# main_scheme.net
KiCad netlist of a schematic drawn in Altium Designer
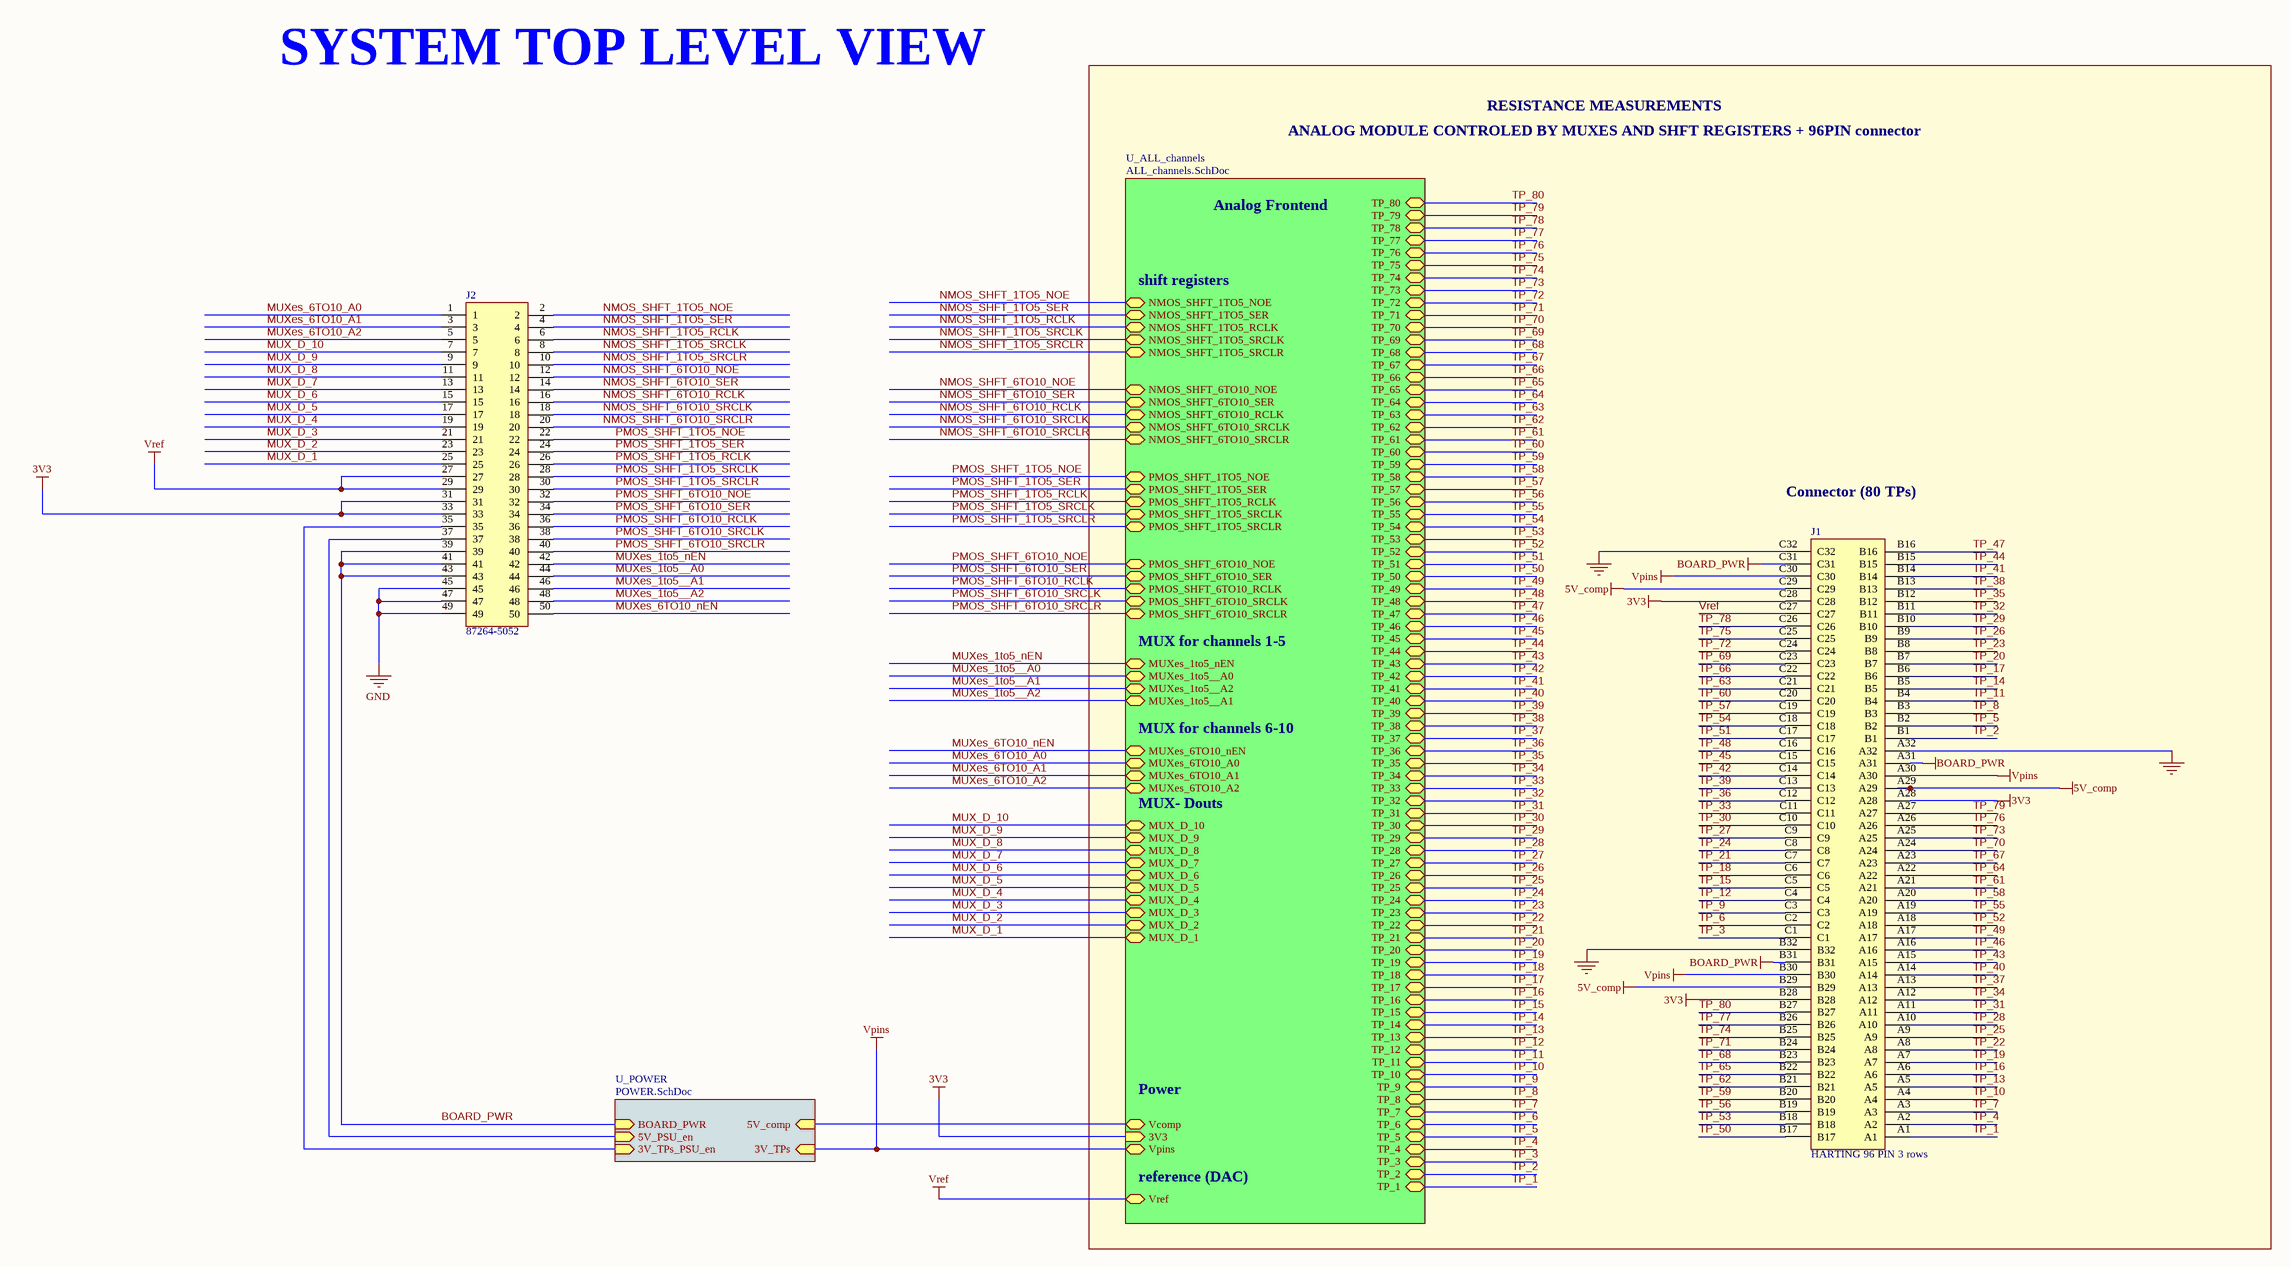
[diagram p0: main_scheme.SchDoc]

(export (version "E")
  (design (tool "Eeschema 10.0.6"))
  (components
    (comp (ref "J1")
      (value "HARTING 96 PIN 3 rows")
      (footprint "PcbLib1:09033966921")
      (description "Connector")
      (fields
        (field (name "MANUFACTURER_PART_NUMBER") "09033966921")
        (field (name "MOUSER PART NUMBER") "617-09-03-396-6921")
      )
      (libsource (lib "Schlib1") (part "HARTING 96 PIN 3 rows"))
    )
    (comp (ref "J2")
      (value "87264-5052")
      (footprint "SamacSys:872645052")
      (description "Connector")
      (fields (field (name "MOUSER PART NUMBER") "538-87264-5052"))
      (libsource (lib "*") (part "87264-5052"))
    )
  )
  (nets
    (net (code "1") (name "/3V_TPs_PSU_en") (class "Default")
      (node (ref "J2") (pin "35") (pinfunction "35_35") (pintype "passive"))
    )
    (net (code "2") (name "/5V_PSU_en") (class "Default")
      (node (ref "J2") (pin "37") (pinfunction "37_37") (pintype "passive"))
    )
    (net (code "4") (name "/MUX_D_1") (class "Default")
      (node (ref "J2") (pin "25") (pinfunction "25_25") (pintype "passive"))
    )
    (net (code "5") (name "/MUX_D_2") (class "Default")
      (node (ref "J2") (pin "23") (pinfunction "23_23") (pintype "passive"))
    )
    (net (code "6") (name "/MUX_D_3") (class "Default")
      (node (ref "J2") (pin "21") (pinfunction "21_21") (pintype "passive"))
    )
    (net (code "7") (name "/MUX_D_4") (class "Default")
      (node (ref "J2") (pin "19") (pinfunction "19_19") (pintype "passive"))
    )
    (net (code "8") (name "/MUX_D_5") (class "Default")
      (node (ref "J2") (pin "17") (pinfunction "17_17") (pintype "passive"))
    )
    (net (code "9") (name "/MUX_D_6") (class "Default")
      (node (ref "J2") (pin "15") (pinfunction "15_15") (pintype "passive"))
    )
    (net (code "10") (name "/MUX_D_7") (class "Default")
      (node (ref "J2") (pin "13") (pinfunction "13_13") (pintype "passive"))
    )
    (net (code "11") (name "/MUX_D_8") (class "Default")
      (node (ref "J2") (pin "11") (pinfunction "11_11") (pintype "passive"))
    )
    (net (code "12") (name "/MUX_D_9") (class "Default")
      (node (ref "J2") (pin "9") (pinfunction "9_9") (pintype "passive"))
    )
    (net (code "13") (name "/MUX_D_10") (class "Default")
      (node (ref "J2") (pin "7") (pinfunction "7_7") (pintype "passive"))
    )
    (net (code "14") (name "/MUXes_1to5__A0") (class "Default")
      (node (ref "J2") (pin "44") (pinfunction "44_44") (pintype "passive"))
    )
    (net (code "15") (name "/MUXes_1to5__A1") (class "Default")
      (node (ref "J2") (pin "46") (pinfunction "46_46") (pintype "passive"))
    )
    (net (code "16") (name "/MUXes_1to5__A2") (class "Default")
      (node (ref "J2") (pin "48") (pinfunction "48_48") (pintype "passive"))
    )
    (net (code "17") (name "/MUXes_1to5_nEN") (class "Default")
      (node (ref "J2") (pin "42") (pinfunction "42_42") (pintype "passive"))
    )
    (net (code "18") (name "/MUXes_6TO10_A0") (class "Default")
      (node (ref "J2") (pin "1") (pinfunction "1_1") (pintype "passive"))
    )
    (net (code "19") (name "/MUXes_6TO10_A1") (class "Default")
      (node (ref "J2") (pin "3") (pinfunction "3_3") (pintype "passive"))
    )
    (net (code "20") (name "/MUXes_6TO10_A2") (class "Default")
      (node (ref "J2") (pin "5") (pinfunction "5_5") (pintype "passive"))
    )
    (net (code "21") (name "/MUXes_6TO10_nEN") (class "Default")
      (node (ref "J2") (pin "50") (pinfunction "50_50") (pintype "passive"))
    )
    (net (code "22") (name "/NMOS_SHFT_1TO5_NOE") (class "Default")
      (node (ref "J2") (pin "2") (pinfunction "2_2") (pintype "passive"))
    )
    (net (code "23") (name "/NMOS_SHFT_1TO5_RCLK") (class "Default")
      (node (ref "J2") (pin "6") (pinfunction "6_6") (pintype "passive"))
    )
    (net (code "24") (name "/NMOS_SHFT_1TO5_SER") (class "Default")
      (node (ref "J2") (pin "4") (pinfunction "4_4") (pintype "passive"))
    )
    (net (code "25") (name "/NMOS_SHFT_1TO5_SRCLK") (class "Default")
      (node (ref "J2") (pin "8") (pinfunction "8_8") (pintype "passive"))
    )
    (net (code "26") (name "/NMOS_SHFT_1TO5_SRCLR") (class "Default")
      (node (ref "J2") (pin "10") (pinfunction "10_10") (pintype "passive"))
    )
    (net (code "27") (name "/NMOS_SHFT_6TO10_NOE") (class "Default")
      (node (ref "J2") (pin "12") (pinfunction "12_12") (pintype "passive"))
    )
    (net (code "28") (name "/NMOS_SHFT_6TO10_RCLK") (class "Default")
      (node (ref "J2") (pin "16") (pinfunction "16_16") (pintype "passive"))
    )
    (net (code "29") (name "/NMOS_SHFT_6TO10_SER") (class "Default")
      (node (ref "J2") (pin "14") (pinfunction "14_14") (pintype "passive"))
    )
    (net (code "30") (name "/NMOS_SHFT_6TO10_SRCLK") (class "Default")
      (node (ref "J2") (pin "18") (pinfunction "18_18") (pintype "passive"))
    )
    (net (code "31") (name "/NMOS_SHFT_6TO10_SRCLR") (class "Default")
      (node (ref "J2") (pin "20") (pinfunction "20_20") (pintype "passive"))
    )
    (net (code "32") (name "/PMOS_SHFT_1TO5_NOE") (class "Default")
      (node (ref "J2") (pin "22") (pinfunction "22_22") (pintype "passive"))
    )
    (net (code "33") (name "/PMOS_SHFT_1TO5_RCLK") (class "Default")
      (node (ref "J2") (pin "26") (pinfunction "26_26") (pintype "passive"))
    )
    (net (code "34") (name "/PMOS_SHFT_1TO5_SER") (class "Default")
      (node (ref "J2") (pin "24") (pinfunction "24_24") (pintype "passive"))
    )
    (net (code "35") (name "/PMOS_SHFT_1TO5_SRCLK") (class "Default")
      (node (ref "J2") (pin "28") (pinfunction "28_28") (pintype "passive"))
    )
    (net (code "36") (name "/PMOS_SHFT_1TO5_SRCLR") (class "Default")
      (node (ref "J2") (pin "30") (pinfunction "30_30") (pintype "passive"))
    )
    (net (code "37") (name "/PMOS_SHFT_6TO10_NOE") (class "Default")
      (node (ref "J2") (pin "32") (pinfunction "32_32") (pintype "passive"))
    )
    (net (code "38") (name "/PMOS_SHFT_6TO10_RCLK") (class "Default")
      (node (ref "J2") (pin "36") (pinfunction "36_36") (pintype "passive"))
    )
    (net (code "39") (name "/PMOS_SHFT_6TO10_SER") (class "Default")
      (node (ref "J2") (pin "34") (pinfunction "34_34") (pintype "passive"))
    )
    (net (code "40") (name "/PMOS_SHFT_6TO10_SRCLK") (class "Default")
      (node (ref "J2") (pin "38") (pinfunction "38_38") (pintype "passive"))
    )
    (net (code "41") (name "/PMOS_SHFT_6TO10_SRCLR") (class "Default")
      (node (ref "J2") (pin "40") (pinfunction "40_40") (pintype "passive"))
    )
    (net (code "42") (name "/TP_1") (class "Default")
      (node (ref "J1") (pin "A1") (pinfunction "A1_A1") (pintype "passive"))
    )
    (net (code "43") (name "/TP_2") (class "Default")
      (node (ref "J1") (pin "B1") (pinfunction "B1_B1") (pintype "passive"))
    )
    (net (code "44") (name "/TP_3") (class "Default")
      (node (ref "J1") (pin "C1") (pinfunction "C1_C1") (pintype "passive"))
    )
    (net (code "45") (name "/TP_4") (class "Default")
      (node (ref "J1") (pin "A2") (pinfunction "A2_A2") (pintype "passive"))
    )
    (net (code "46") (name "/TP_5") (class "Default")
      (node (ref "J1") (pin "B2") (pinfunction "B2_B2") (pintype "passive"))
    )
    (net (code "47") (name "/TP_6") (class "Default")
      (node (ref "J1") (pin "C2") (pinfunction "C2_C2") (pintype "passive"))
    )
    (net (code "48") (name "/TP_7") (class "Default")
      (node (ref "J1") (pin "A3") (pinfunction "A3_A3") (pintype "passive"))
    )
    (net (code "49") (name "/TP_8") (class "Default")
      (node (ref "J1") (pin "B3") (pinfunction "B3_B3") (pintype "passive"))
    )
    (net (code "50") (name "/TP_9") (class "Default")
      (node (ref "J1") (pin "C3") (pinfunction "C3_C3") (pintype "passive"))
    )
    (net (code "51") (name "/TP_10") (class "Default")
      (node (ref "J1") (pin "A4") (pinfunction "A4_A4") (pintype "passive"))
    )
    (net (code "52") (name "/TP_11") (class "Default")
      (node (ref "J1") (pin "B4") (pinfunction "B4_B4") (pintype "passive"))
    )
    (net (code "53") (name "/TP_12") (class "Default")
      (node (ref "J1") (pin "C4") (pinfunction "C4_C4") (pintype "passive"))
    )
    (net (code "54") (name "/TP_13") (class "Default")
      (node (ref "J1") (pin "A5") (pinfunction "A5_A5") (pintype "passive"))
    )
    (net (code "55") (name "/TP_14") (class "Default")
      (node (ref "J1") (pin "B5") (pinfunction "B5_B5") (pintype "passive"))
    )
    (net (code "56") (name "/TP_15") (class "Default")
      (node (ref "J1") (pin "C5") (pinfunction "C5_C5") (pintype "passive"))
    )
    (net (code "57") (name "/TP_16") (class "Default")
      (node (ref "J1") (pin "A6") (pinfunction "A6_A6") (pintype "passive"))
    )
    (net (code "58") (name "/TP_17") (class "Default")
      (node (ref "J1") (pin "B6") (pinfunction "B6_B6") (pintype "passive"))
    )
    (net (code "59") (name "/TP_18") (class "Default")
      (node (ref "J1") (pin "C6") (pinfunction "C6_C6") (pintype "passive"))
    )
    (net (code "60") (name "/TP_19") (class "Default")
      (node (ref "J1") (pin "A7") (pinfunction "A7_A7") (pintype "passive"))
    )
    (net (code "61") (name "/TP_20") (class "Default")
      (node (ref "J1") (pin "B7") (pinfunction "B7_B7") (pintype "passive"))
    )
    (net (code "62") (name "/TP_21") (class "Default")
      (node (ref "J1") (pin "C7") (pinfunction "C7_C7") (pintype "passive"))
    )
    (net (code "63") (name "/TP_22") (class "Default")
      (node (ref "J1") (pin "A8") (pinfunction "A8_A8") (pintype "passive"))
    )
    (net (code "64") (name "/TP_23") (class "Default")
      (node (ref "J1") (pin "B8") (pinfunction "B8_B8") (pintype "passive"))
    )
    (net (code "65") (name "/TP_24") (class "Default")
      (node (ref "J1") (pin "C8") (pinfunction "C8_C8") (pintype "passive"))
    )
    (net (code "66") (name "/TP_25") (class "Default")
      (node (ref "J1") (pin "A9") (pinfunction "A9_A9") (pintype "passive"))
    )
    (net (code "67") (name "/TP_26") (class "Default")
      (node (ref "J1") (pin "B9") (pinfunction "B9_B9") (pintype "passive"))
    )
    (net (code "68") (name "/TP_27") (class "Default")
      (node (ref "J1") (pin "C9") (pinfunction "C9_C9") (pintype "passive"))
    )
    (net (code "69") (name "/TP_28") (class "Default")
      (node (ref "J1") (pin "A10") (pinfunction "A10_A10") (pintype "passive"))
    )
    (net (code "70") (name "/TP_29") (class "Default")
      (node (ref "J1") (pin "B10") (pinfunction "B10_B10") (pintype "passive"))
    )
    (net (code "71") (name "/TP_30") (class "Default")
      (node (ref "J1") (pin "C10") (pinfunction "C10_C10") (pintype "passive"))
    )
    (net (code "72") (name "/TP_31") (class "Default")
      (node (ref "J1") (pin "A11") (pinfunction "A11_A11") (pintype "passive"))
    )
    (net (code "73") (name "/TP_32") (class "Default")
      (node (ref "J1") (pin "B11") (pinfunction "B11_B11") (pintype "passive"))
    )
    (net (code "74") (name "/TP_33") (class "Default")
      (node (ref "J1") (pin "C11") (pinfunction "C11_C11") (pintype "passive"))
    )
    (net (code "75") (name "/TP_34") (class "Default")
      (node (ref "J1") (pin "A12") (pinfunction "A12_A12") (pintype "passive"))
    )
    (net (code "76") (name "/TP_35") (class "Default")
      (node (ref "J1") (pin "B12") (pinfunction "B12_B12") (pintype "passive"))
    )
    (net (code "77") (name "/TP_36") (class "Default")
      (node (ref "J1") (pin "C12") (pinfunction "C12_C12") (pintype "passive"))
    )
    (net (code "78") (name "/TP_37") (class "Default")
      (node (ref "J1") (pin "A13") (pinfunction "A13_A13") (pintype "passive"))
    )
    (net (code "79") (name "/TP_38") (class "Default")
      (node (ref "J1") (pin "B13") (pinfunction "B13_B13") (pintype "passive"))
    )
    (net (code "80") (name "/TP_39") (class "Default")
      (node (ref "J1") (pin "C13") (pinfunction "C13_C13") (pintype "passive"))
    )
    (net (code "81") (name "/TP_40") (class "Default")
      (node (ref "J1") (pin "A14") (pinfunction "A14_A14") (pintype "passive"))
    )
    (net (code "82") (name "/TP_41") (class "Default")
      (node (ref "J1") (pin "B14") (pinfunction "B14_B14") (pintype "passive"))
    )
    (net (code "83") (name "/TP_42") (class "Default")
      (node (ref "J1") (pin "C14") (pinfunction "C14_C14") (pintype "passive"))
    )
    (net (code "84") (name "/TP_43") (class "Default")
      (node (ref "J1") (pin "A15") (pinfunction "A15_A15") (pintype "passive"))
    )
    (net (code "85") (name "/TP_44") (class "Default")
      (node (ref "J1") (pin "B15") (pinfunction "B15_B15") (pintype "passive"))
    )
    (net (code "86") (name "/TP_45") (class "Default")
      (node (ref "J1") (pin "C15") (pinfunction "C15_C15") (pintype "passive"))
    )
    (net (code "87") (name "/TP_46") (class "Default")
      (node (ref "J1") (pin "A16") (pinfunction "A16_A16") (pintype "passive"))
    )
    (net (code "88") (name "/TP_47") (class "Default")
      (node (ref "J1") (pin "B16") (pinfunction "B16_B16") (pintype "passive"))
    )
    (net (code "89") (name "/TP_48") (class "Default")
      (node (ref "J1") (pin "C16") (pinfunction "C16_C16") (pintype "passive"))
    )
    (net (code "90") (name "/TP_49") (class "Default")
      (node (ref "J1") (pin "A17") (pinfunction "A17_A17") (pintype "passive"))
    )
    (net (code "91") (name "/TP_50") (class "Default")
      (node (ref "J1") (pin "B17") (pinfunction "B17_B17") (pintype "passive"))
    )
    (net (code "92") (name "/TP_51") (class "Default")
      (node (ref "J1") (pin "C17") (pinfunction "C17_C17") (pintype "passive"))
    )
    (net (code "93") (name "/TP_52") (class "Default")
      (node (ref "J1") (pin "A18") (pinfunction "A18_A18") (pintype "passive"))
    )
    (net (code "94") (name "/TP_53") (class "Default")
      (node (ref "J1") (pin "B18") (pinfunction "B18_B18") (pintype "passive"))
    )
    (net (code "95") (name "/TP_54") (class "Default")
      (node (ref "J1") (pin "C18") (pinfunction "C18_C18") (pintype "passive"))
    )
    (net (code "96") (name "/TP_55") (class "Default")
      (node (ref "J1") (pin "A19") (pinfunction "A19_A19") (pintype "passive"))
    )
    (net (code "97") (name "/TP_56") (class "Default")
      (node (ref "J1") (pin "B19") (pinfunction "B19_B19") (pintype "passive"))
    )
    (net (code "98") (name "/TP_57") (class "Default")
      (node (ref "J1") (pin "C19") (pinfunction "C19_C19") (pintype "passive"))
    )
    (net (code "99") (name "/TP_58") (class "Default")
      (node (ref "J1") (pin "A20") (pinfunction "A20_A20") (pintype "passive"))
    )
    (net (code "100") (name "/TP_59") (class "Default")
      (node (ref "J1") (pin "B20") (pinfunction "B20_B20") (pintype "passive"))
    )
    (net (code "101") (name "/TP_60") (class "Default")
      (node (ref "J1") (pin "C20") (pinfunction "C20_C20") (pintype "passive"))
    )
    (net (code "102") (name "/TP_61") (class "Default")
      (node (ref "J1") (pin "A21") (pinfunction "A21_A21") (pintype "passive"))
    )
    (net (code "103") (name "/TP_62") (class "Default")
      (node (ref "J1") (pin "B21") (pinfunction "B21_B21") (pintype "passive"))
    )
    (net (code "104") (name "/TP_63") (class "Default")
      (node (ref "J1") (pin "C21") (pinfunction "C21_C21") (pintype "passive"))
    )
    (net (code "105") (name "/TP_64") (class "Default")
      (node (ref "J1") (pin "A22") (pinfunction "A22_A22") (pintype "passive"))
    )
    (net (code "106") (name "/TP_65") (class "Default")
      (node (ref "J1") (pin "B22") (pinfunction "B22_B22") (pintype "passive"))
    )
    (net (code "107") (name "/TP_66") (class "Default")
      (node (ref "J1") (pin "C22") (pinfunction "C22_C22") (pintype "passive"))
    )
    (net (code "108") (name "/TP_67") (class "Default")
      (node (ref "J1") (pin "A23") (pinfunction "A23_A23") (pintype "passive"))
    )
    (net (code "109") (name "/TP_68") (class "Default")
      (node (ref "J1") (pin "B23") (pinfunction "B23_B23") (pintype "passive"))
    )
    (net (code "110") (name "/TP_69") (class "Default")
      (node (ref "J1") (pin "C23") (pinfunction "C23_C23") (pintype "passive"))
    )
    (net (code "111") (name "/TP_70") (class "Default")
      (node (ref "J1") (pin "A24") (pinfunction "A24_A24") (pintype "passive"))
    )
    (net (code "112") (name "/TP_71") (class "Default")
      (node (ref "J1") (pin "B24") (pinfunction "B24_B24") (pintype "passive"))
    )
    (net (code "113") (name "/TP_72") (class "Default")
      (node (ref "J1") (pin "C24") (pinfunction "C24_C24") (pintype "passive"))
    )
    (net (code "114") (name "/TP_73") (class "Default")
      (node (ref "J1") (pin "A25") (pinfunction "A25_A25") (pintype "passive"))
    )
    (net (code "115") (name "/TP_74") (class "Default")
      (node (ref "J1") (pin "B25") (pinfunction "B25_B25") (pintype "passive"))
    )
    (net (code "116") (name "/TP_75") (class "Default")
      (node (ref "J1") (pin "C25") (pinfunction "C25_C25") (pintype "passive"))
    )
    (net (code "117") (name "/TP_76") (class "Default")
      (node (ref "J1") (pin "A26") (pinfunction "A26_A26") (pintype "passive"))
    )
    (net (code "118") (name "/TP_77") (class "Default")
      (node (ref "J1") (pin "B26") (pinfunction "B26_B26") (pintype "passive"))
    )
    (net (code "119") (name "/TP_78") (class "Default")
      (node (ref "J1") (pin "C26") (pinfunction "C26_C26") (pintype "passive"))
    )
    (net (code "120") (name "/TP_79") (class "Default")
      (node (ref "J1") (pin "A27") (pinfunction "A27_A27") (pintype "passive"))
    )
    (net (code "121") (name "/TP_80") (class "Default")
      (node (ref "J1") (pin "B27") (pinfunction "B27_B27") (pintype "passive"))
    )
    (net (code "122") (name "3V3") (class "Default")
      (node (ref "J1") (pin "A28") (pinfunction "A28_A28") (pintype "passive"))
      (node (ref "J1") (pin "B28") (pinfunction "B28_B28") (pintype "passive"))
      (node (ref "J1") (pin "C28") (pinfunction "C28_C28") (pintype "passive"))
      (node (ref "J2") (pin "31") (pinfunction "31_31") (pintype "passive"))
      (node (ref "J2") (pin "33") (pinfunction "33_33") (pintype "passive"))
    )
    (net (code "123") (name "5V_comp") (class "Default")
      (node (ref "J1") (pin "A29") (pinfunction "A29_A29") (pintype "passive"))
      (node (ref "J1") (pin "B29") (pinfunction "B29_B29") (pintype "passive"))
      (node (ref "J1") (pin "C29") (pinfunction "C29_C29") (pintype "passive"))
    )
    (net (code "124") (name "BOARD_PWR") (class "Default")
      (node (ref "J1") (pin "A31") (pinfunction "A31_A31") (pintype "passive"))
      (node (ref "J1") (pin "B31") (pinfunction "B31_B31") (pintype "passive"))
      (node (ref "J1") (pin "C31") (pinfunction "C31_C31") (pintype "passive"))
      (node (ref "J2") (pin "39") (pinfunction "39_39") (pintype "passive"))
      (node (ref "J2") (pin "41") (pinfunction "41_41") (pintype "passive"))
      (node (ref "J2") (pin "43") (pinfunction "43_43") (pintype "passive"))
    )
    (net (code "125") (name "GND") (class "Default")
      (node (ref "J1") (pin "A32") (pinfunction "A32_A32") (pintype "passive"))
      (node (ref "J1") (pin "B32") (pinfunction "B32_B32") (pintype "passive"))
      (node (ref "J1") (pin "C32") (pinfunction "C32_C32") (pintype "passive"))
      (node (ref "J2") (pin "45") (pinfunction "45_45") (pintype "passive"))
      (node (ref "J2") (pin "47") (pinfunction "47_47") (pintype "passive"))
      (node (ref "J2") (pin "49") (pinfunction "49_49") (pintype "passive"))
    )
    (net (code "126") (name "Vpins") (class "Default")
      (node (ref "J1") (pin "A30") (pinfunction "A30_A30") (pintype "passive"))
      (node (ref "J1") (pin "B30") (pinfunction "B30_B30") (pintype "passive"))
      (node (ref "J1") (pin "C30") (pinfunction "C30_C30") (pintype "passive"))
    )
    (net (code "127") (name "Vref") (class "Default")
      (node (ref "J1") (pin "C27") (pinfunction "C27_C27") (pintype "passive"))
      (node (ref "J2") (pin "27") (pinfunction "27_27") (pintype "passive"))
      (node (ref "J2") (pin "29") (pinfunction "29_29") (pintype "passive"))
    )
  )
)
